# MiniDC2.net
KiCad netlist of a schematic drawn in EAGLE
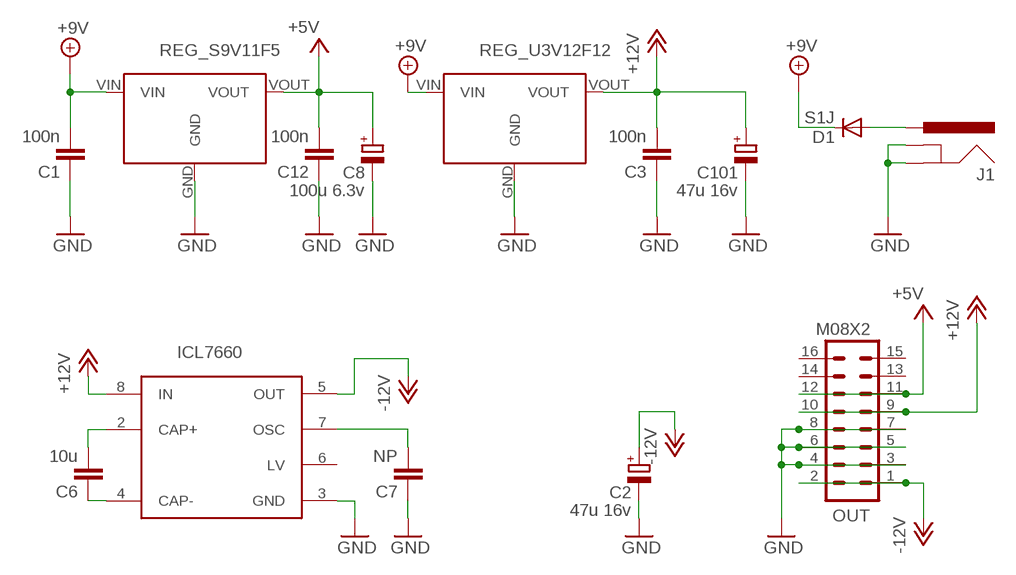
[diagram p0: schematic, sheet 1]

(export (version "E")
  (design (tool "Eeschema 10.0.6"))
  (components
    (comp (ref "C1")
      (value "100n")
      (footprint "eagle-import:C0603")
      (libsource (lib "eagle-import") (part "C-EUC0603"))
    )
    (comp (ref "C2")
      (value "47u 16v")
      (footprint "eagle-import:PANASONIC_B")
      (libsource (lib "eagle-import") (part "CPOL-EUB"))
    )
    (comp (ref "C3")
      (value "100n")
      (footprint "eagle-import:C0603")
      (libsource (lib "eagle-import") (part "C-EUC0603"))
    )
    (comp (ref "C6")
      (value "10u")
      (footprint "eagle-import:C1206")
      (libsource (lib "eagle-import") (part "C-EUC1206"))
    )
    (comp (ref "C7")
      (value "NP")
      (footprint "eagle-import:C0603")
      (libsource (lib "eagle-import") (part "C-EUC0603"))
    )
    (comp (ref "C8")
      (value "100u 6.3v")
      (footprint "eagle-import:PANASONIC_B")
      (libsource (lib "eagle-import") (part "CPOL-EUB"))
    )
    (comp (ref "C12")
      (value "100n")
      (footprint "eagle-import:C0603")
      (libsource (lib "eagle-import") (part "C-EUC0603"))
    )
    (comp (ref "C101")
      (value "47u 16v")
      (footprint "eagle-import:PANASONIC_B")
      (libsource (lib "eagle-import") (part "CPOL-EUB"))
    )
    (comp (ref "D1")
      (value "S1J")
      (footprint "eagle-import:SMA-DIODE")
      (libsource (lib "eagle-import") (part "DIODESMA"))
    )
    (comp (ref "J1")
      (value "POWER_JACKPTH")
      (footprint "eagle-import:POWER_JACK_PTH")
      (libsource (lib "eagle-import") (part "POWER_JACKPTH"))
    )
    (comp (ref "OUT")
      (value "M08X2")
      (footprint "eagle-import:2X8")
      (libsource (lib "eagle-import") (part "M08X2"))
    )
    (comp (ref "U1")
      (value "REG_S9V11F5")
      (footprint "eagle-import:REG_S9V11F5")
      (libsource (lib "eagle-import") (part "REG_S9V11F5"))
    )
    (comp (ref "U2")
      (value "REG_U3V12F12")
      (footprint "eagle-import:REG_S9V11F5")
      (libsource (lib "eagle-import") (part "REG_S9V11F5"))
    )
    (comp (ref "U3")
      (value "ICL7660")
      (footprint "eagle-import:SOIC8")
      (libsource (lib "eagle-import") (part "ICL7660"))
    )
  )
  (nets
    (net (code "1") (name "+5V") (class "Default")
      (node (ref "C12") (pin "2") (pinfunction "2_2") (pintype "passive"))
      (node (ref "C8") (pin "+") (pinfunction "+_+") (pintype "passive"))
      (node (ref "OUT") (pin "11") (pinfunction "11_11") (pintype "passive"))
      (node (ref "OUT") (pin "12") (pinfunction "12_12") (pintype "passive"))
      (node (ref "U1") (pin "VOUT") (pinfunction "VOUT_VOUT") (pintype "output"))
    )
    (net (code "2") (name "+9V") (class "Default")
      (node (ref "C1") (pin "2") (pinfunction "2_2") (pintype "passive"))
      (node (ref "D1") (pin "C") (pinfunction "C_C") (pintype "passive"))
      (node (ref "U1") (pin "VIN") (pinfunction "VIN_VIN") (pintype "input"))
      (node (ref "U2") (pin "VIN") (pinfunction "VIN_VIN") (pintype "input"))
    )
    (net (code "3") (name "+12V") (class "Default")
      (node (ref "C101") (pin "+") (pinfunction "+_+") (pintype "passive"))
      (node (ref "C3") (pin "2") (pinfunction "2_2") (pintype "passive"))
      (node (ref "OUT") (pin "10") (pinfunction "10_10") (pintype "passive"))
      (node (ref "OUT") (pin "9") (pinfunction "9_9") (pintype "passive"))
      (node (ref "U2") (pin "VOUT") (pinfunction "VOUT_VOUT") (pintype "output"))
      (node (ref "U3") (pin "8") (pinfunction "IN_8") (pintype "bidirectional"))
    )
    (net (code "4") (name "-12V") (class "Default")
      (node (ref "C2") (pin "+") (pinfunction "+_+") (pintype "passive"))
      (node (ref "OUT") (pin "1") (pinfunction "1_1") (pintype "passive"))
      (node (ref "OUT") (pin "2") (pinfunction "2_2") (pintype "passive"))
      (node (ref "U3") (pin "5") (pinfunction "OUT_5") (pintype "bidirectional"))
    )
    (net (code "5") (name "GND") (class "Default")
      (node (ref "C1") (pin "1") (pinfunction "1_1") (pintype "passive"))
      (node (ref "C101") (pin "-") (pinfunction "-_-") (pintype "passive"))
      (node (ref "C12") (pin "1") (pinfunction "1_1") (pintype "passive"))
      (node (ref "C2") (pin "-") (pinfunction "-_-") (pintype "passive"))
      (node (ref "C3") (pin "1") (pinfunction "1_1") (pintype "passive"))
      (node (ref "C7") (pin "1") (pinfunction "1_1") (pintype "passive"))
      (node (ref "C8") (pin "-") (pinfunction "-_-") (pintype "passive"))
      (node (ref "J1") (pin "GND") (pinfunction "GND_GND") (pintype "bidirectional"))
      (node (ref "J1") (pin "GNDBREAK") (pinfunction "GNDBREAK_GNDBREAK") (pintype "bidirectional"))
      (node (ref "OUT") (pin "3") (pinfunction "3_3") (pintype "passive"))
      (node (ref "OUT") (pin "4") (pinfunction "4_4") (pintype "passive"))
      (node (ref "OUT") (pin "5") (pinfunction "5_5") (pintype "passive"))
      (node (ref "OUT") (pin "6") (pinfunction "6_6") (pintype "passive"))
      (node (ref "OUT") (pin "7") (pinfunction "7_7") (pintype "passive"))
      (node (ref "OUT") (pin "8") (pinfunction "8_8") (pintype "passive"))
      (node (ref "U1") (pin "GND") (pinfunction "GND_GND") (pintype "power_in"))
      (node (ref "U2") (pin "GND") (pinfunction "GND_GND") (pintype "power_in"))
      (node (ref "U3") (pin "3") (pinfunction "GND_3") (pintype "bidirectional"))
    )
    (net (code "6") (name "Net-(D1-PadA)") (class "Default")
      (node (ref "D1") (pin "A") (pinfunction "A_A") (pintype "passive"))
      (node (ref "J1") (pin "PWR") (pinfunction "PWR_PWR") (pintype "bidirectional"))
    )
    (net (code "7") (name "Net-(U3-CAP+)") (class "Default")
      (node (ref "C6") (pin "2") (pinfunction "2_2") (pintype "passive"))
      (node (ref "U3") (pin "2") (pinfunction "CAP+_2") (pintype "bidirectional"))
    )
    (net (code "8") (name "Net-(U3-CAP-)") (class "Default")
      (node (ref "C6") (pin "1") (pinfunction "1_1") (pintype "passive"))
      (node (ref "U3") (pin "4") (pinfunction "CAP-_4") (pintype "bidirectional"))
    )
    (net (code "9") (name "Net-(U3-OSC)") (class "Default")
      (node (ref "C7") (pin "2") (pinfunction "2_2") (pintype "passive"))
      (node (ref "U3") (pin "7") (pinfunction "OSC_7") (pintype "bidirectional"))
    )
    (net (code "10") (name "unconnected-(OUT-Pad13)") (class "Default")
      (node (ref "OUT") (pin "13") (pinfunction "13_13") (pintype "passive"))
    )
    (net (code "11") (name "unconnected-(OUT-Pad14)") (class "Default")
      (node (ref "OUT") (pin "14") (pinfunction "14_14") (pintype "passive"))
    )
    (net (code "12") (name "unconnected-(OUT-Pad15)") (class "Default")
      (node (ref "OUT") (pin "15") (pinfunction "15_15") (pintype "passive"))
    )
    (net (code "13") (name "unconnected-(OUT-Pad16)") (class "Default")
      (node (ref "OUT") (pin "16") (pinfunction "16_16") (pintype "passive"))
    )
    (net (code "14") (name "unconnected-(U3-LV-Pad6)") (class "Default")
      (node (ref "U3") (pin "6") (pinfunction "LV_6") (pintype "bidirectional"))
    )
  )
)
